# regulators.net
KiCad netlist of a schematic drawn in Altium Designer
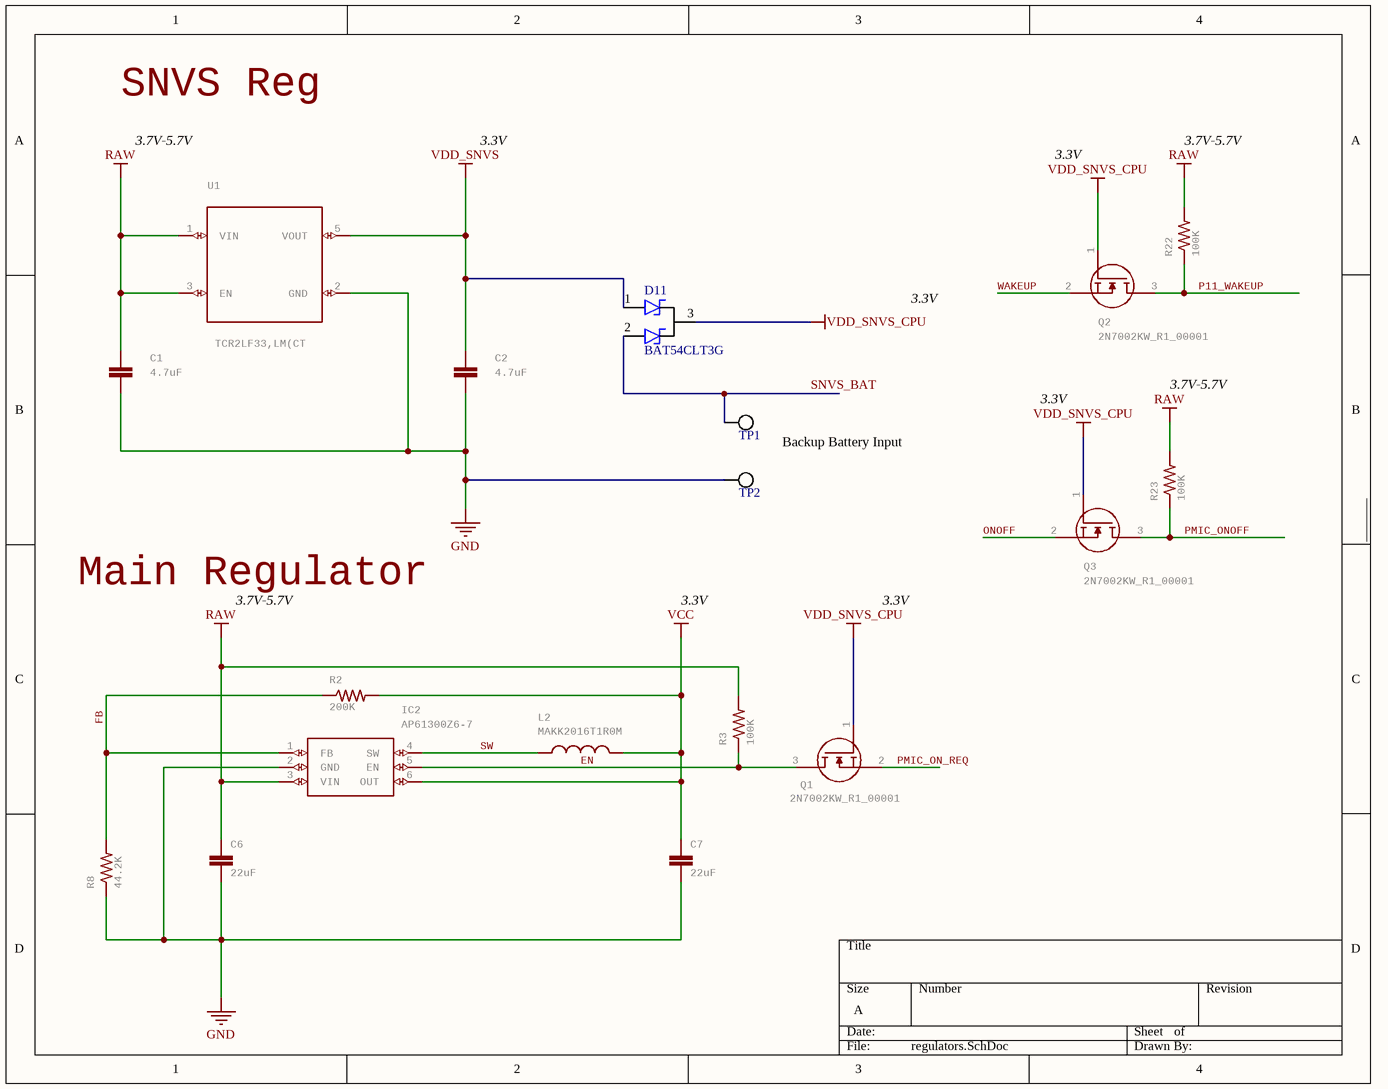
[diagram p0: regulators.SchDoc]

(export (version "E")
  (design (tool "Eeschema 10.0.6"))
  (components
    (comp (ref "C1")
      (value "4.7uF")
      (footprint "0402-CAP")
      (description "CapacitorStandard 0603 ceramic capacitor, and 0.1\" leaded capacitor.")
      (fields (field (name "MPN") "JMK105BBJ475MV-F"))
      (libsource (lib "rt10") (part "CAP0402-CAP"))
    )
    (comp (ref "C2")
      (value "4.7uF")
      (footprint "0402-CAP")
      (description "CapacitorStandard 0603 ceramic capacitor, and 0.1\" leaded capacitor.")
      (fields (field (name "MPN") "JMK105BBJ475MV-F"))
      (libsource (lib "rt10") (part "CAP0402-CAP"))
    )
    (comp (ref "C6")
      (value "22uF")
      (footprint "0805")
      (fields (field (name "MPN") "CL21A226MQQNNNE"))
      (libsource (lib "rt10") (part "22UF-0805-6.3V-20%"))
    )
    (comp (ref "C7")
      (value "22uF")
      (footprint "0805")
      (fields (field (name "MPN") "CL21A226MQQNNNE"))
      (libsource (lib "rt10") (part "22UF-0805-6.3V-20%"))
    )
    (comp (ref "D11")
      (value "Dual Schottky")
      (footprint "SOT-23-3")
      (fields (field (name "MPN") "BAT54CLT3G") (field (name "PART NUMBER") "BAT54CLT3G"))
      (libsource (lib "rt10") (part "Dual Schottky"))
    )
    (comp (ref "IC2")
      (value "AP61300Z6-7")
      (footprint "SOTFL50P162X60-6N")
      (description "DCDC Conv LV Buck SOT563 T&R 3K   Source:  Datasheet")
      (fields (field (name "MOUSER_PART_NUMBER") "621-AP61300Z6-7"))
      (libsource (lib "rt10") (part "AP61300Z6-7"))
    )
    (comp (ref "L2")
      (value "MAKK2016T1R0M")
      (footprint "INDC2016X100N")
      (description "Ind Power Wirewound 1uH 20% 2MHz Metal 2200mA 0806 Check availability")
      (fields (field (name "MF") "Taiyo Yuden"))
      (libsource (lib "rt10") (part "MAKK2016T1R0M"))
    )
    (comp (ref "Q1")
      (value "2N7002KW_R1_00001")
      (footprint "SOT65P210X110-3N")
      (description "MOSFET 60V N-Channel Enhancement Mode MOSFET - ESD Protected   Source:  Datasheet")
      (fields (field (name "MOUSER_PART_NUMBER") "241-2N7002KWR100001"))
      (libsource (lib "rt10") (part "2N7002KW_R1_00001"))
    )
    (comp (ref "Q2")
      (value "2N7002KW_R1_00001")
      (footprint "SOT65P210X110-3N")
      (description "MOSFET 60V N-Channel Enhancement Mode MOSFET - ESD Protected   Source:  Datasheet")
      (fields (field (name "MOUSER_PART_NUMBER") "241-2N7002KWR100001"))
      (libsource (lib "rt10") (part "2N7002KW_R1_00001"))
    )
    (comp (ref "Q3")
      (value "2N7002KW_R1_00001")
      (footprint "SOT65P210X110-3N")
      (description "MOSFET 60V N-Channel Enhancement Mode MOSFET - ESD Protected   Source:  Datasheet")
      (fields (field (name "MOUSER_PART_NUMBER") "241-2N7002KWR100001"))
      (libsource (lib "rt10") (part "2N7002KW_R1_00001"))
    )
    (comp (ref "R2")
      (value "200K")
      (footprint "0402-RES")
      (description "ResistorBasic schematic elements and footprints for 0603, 1206, and PTH resistors.")
      (fields (field (name "MPN") "CRCW0402200KFKEDC"))
      (libsource (lib "rt10") (part "RESISTOR0402-RES"))
    )
    (comp (ref "R3")
      (value "100K")
      (footprint "0402-RES")
      (description "ResistorBasic schematic elements and footprints for 0603, 1206, and PTH resistors.")
      (fields (field (name "MPN") "AC0402FR-07100KL"))
      (libsource (lib "rt10") (part "RESISTOR0402-RES"))
    )
    (comp (ref "R8")
      (value "44.2K")
      (footprint "0402-RES")
      (description "ResistorBasic schematic elements and footprints for 0603, 1206, and PTH resistors.")
      (fields (field (name "MPN") "AC0402FR-0744K2L"))
      (libsource (lib "rt10") (part "RESISTOR0402-RES"))
    )
    (comp (ref "R22")
      (value "100K")
      (footprint "0402-RES")
      (description "ResistorBasic schematic elements and footprints for 0603, 1206, and PTH resistors.")
      (fields (field (name "MPN") "AC0402FR-07100KL"))
      (libsource (lib "rt10") (part "RESISTOR0402-RES"))
    )
    (comp (ref "R23")
      (value "100K")
      (footprint "0402-RES")
      (description "ResistorBasic schematic elements and footprints for 0603, 1206, and PTH resistors.")
      (fields (field (name "MPN") "AC0402FR-07100KL"))
      (libsource (lib "rt10") (part "RESISTOR0402-RES"))
    )
    (comp (ref "TP1") (value "TP") (footprint "TP_1p8") (libsource (lib "rt10") (part "TP")))
    (comp (ref "TP2") (value "TP") (footprint "TP_1p8") (libsource (lib "rt10") (part "TP")))
    (comp (ref "U1")
      (value "TCR2LF33,LM(CT")
      (footprint "SOT-23-5")
      (libsource (lib "rt10") (part "TCR2LF33,LM(CT"))
    )
  )
  (nets
    (net (code "1") (name "/EN") (class "Default")
      (node (ref "IC2") (pin "5") (pinfunction "EN_5") (pintype "bidirectional"))
      (node (ref "Q1") (pin "3") (pinfunction "D_3") (pintype "bidirectional"))
      (node (ref "R3") (pin "1") (pinfunction "1_1") (pintype "passive"))
    )
    (net (code "2") (name "/FB") (class "Default")
      (node (ref "IC2") (pin "1") (pinfunction "FB_1") (pintype "bidirectional"))
      (node (ref "R2") (pin "1") (pinfunction "1_1") (pintype "passive"))
      (node (ref "R8") (pin "2") (pinfunction "2_2") (pintype "passive"))
    )
    (net (code "3") (name "/ONOFF") (class "Default")
      (node (ref "Q3") (pin "2") (pinfunction "S_2") (pintype "bidirectional"))
    )
    (net (code "4") (name "/P11_WAKEUP") (class "Default")
      (node (ref "Q2") (pin "3") (pinfunction "D_3") (pintype "bidirectional"))
      (node (ref "R22") (pin "1") (pinfunction "1_1") (pintype "passive"))
    )
    (net (code "5") (name "/PMIC_ONOFF") (class "Default")
      (node (ref "Q3") (pin "3") (pinfunction "D_3") (pintype "bidirectional"))
      (node (ref "R23") (pin "1") (pinfunction "1_1") (pintype "passive"))
    )
    (net (code "6") (name "/PMIC_ON_REQ") (class "Default")
      (node (ref "Q1") (pin "2") (pinfunction "S_2") (pintype "bidirectional"))
    )
    (net (code "7") (name "/SNVS_BAT") (class "Default")
      (node (ref "D11") (pin "2") (pinfunction "2_2") (pintype "passive"))
      (node (ref "TP1") (pin "1") (pinfunction "1_1") (pintype "passive"))
    )
    (net (code "8") (name "/SW") (class "Default")
      (node (ref "IC2") (pin "4") (pinfunction "SW_4") (pintype "bidirectional"))
      (node (ref "L2") (pin "1") (pinfunction "1_1") (pintype "passive"))
    )
    (net (code "9") (name "/WAKEUP") (class "Default")
      (node (ref "Q2") (pin "2") (pinfunction "S_2") (pintype "bidirectional"))
    )
    (net (code "10") (name "GND") (class "Default")
      (node (ref "C1") (pin "1") (pinfunction "1_1") (pintype "passive"))
      (node (ref "C2") (pin "1") (pinfunction "1_1") (pintype "passive"))
      (node (ref "C6") (pin "2") (pinfunction "2_2") (pintype "passive"))
      (node (ref "C7") (pin "2") (pinfunction "2_2") (pintype "passive"))
      (node (ref "IC2") (pin "2") (pinfunction "GND_2") (pintype "bidirectional"))
      (node (ref "R8") (pin "1") (pinfunction "1_1") (pintype "passive"))
      (node (ref "TP2") (pin "1") (pinfunction "1_1") (pintype "passive"))
      (node (ref "U1") (pin "2") (pinfunction "GND_2") (pintype "bidirectional"))
    )
    (net (code "11") (name "RAW") (class "Default")
      (node (ref "C1") (pin "2") (pinfunction "2_2") (pintype "passive"))
      (node (ref "C6") (pin "1") (pinfunction "1_1") (pintype "passive"))
      (node (ref "IC2") (pin "3") (pinfunction "VIN_3") (pintype "bidirectional"))
      (node (ref "R22") (pin "2") (pinfunction "2_2") (pintype "passive"))
      (node (ref "R23") (pin "2") (pinfunction "2_2") (pintype "passive"))
      (node (ref "R3") (pin "2") (pinfunction "2_2") (pintype "passive"))
      (node (ref "U1") (pin "1") (pinfunction "VIN_1") (pintype "bidirectional"))
      (node (ref "U1") (pin "3") (pinfunction "EN_3") (pintype "bidirectional"))
    )
    (net (code "12") (name "VCC") (class "Default")
      (node (ref "C7") (pin "1") (pinfunction "1_1") (pintype "passive"))
      (node (ref "IC2") (pin "6") (pinfunction "OUT_6") (pintype "bidirectional"))
      (node (ref "L2") (pin "2") (pinfunction "2_2") (pintype "passive"))
      (node (ref "R2") (pin "2") (pinfunction "2_2") (pintype "passive"))
    )
    (net (code "13") (name "VDD_SNVS") (class "Default")
      (node (ref "C2") (pin "2") (pinfunction "2_2") (pintype "passive"))
      (node (ref "D11") (pin "1") (pinfunction "1_1") (pintype "passive"))
      (node (ref "U1") (pin "5") (pinfunction "VOUT_5") (pintype "bidirectional"))
    )
    (net (code "14") (name "VDD_SNVS_CPU") (class "Default")
      (node (ref "D11") (pin "3") (pinfunction "3_3") (pintype "passive"))
      (node (ref "Q1") (pin "1") (pinfunction "G_1") (pintype "bidirectional"))
      (node (ref "Q2") (pin "1") (pinfunction "G_1") (pintype "bidirectional"))
      (node (ref "Q3") (pin "1") (pinfunction "G_1") (pintype "bidirectional"))
    )
  )
)
